# PCU.net
KiCad netlist of a schematic drawn in EAGLE
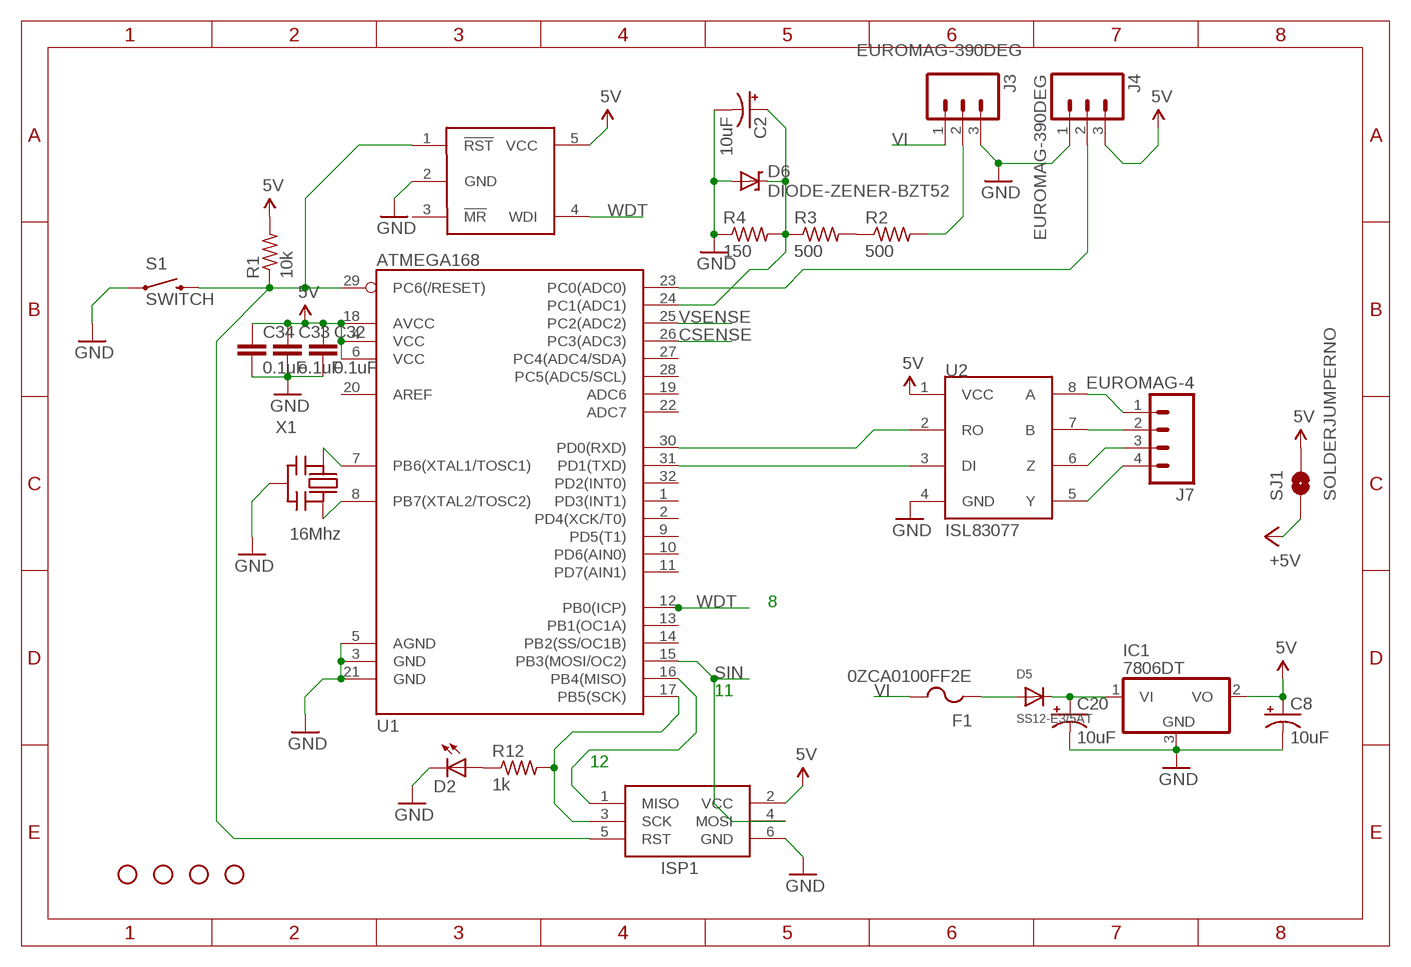
[diagram p0: schematic, sheet 1]
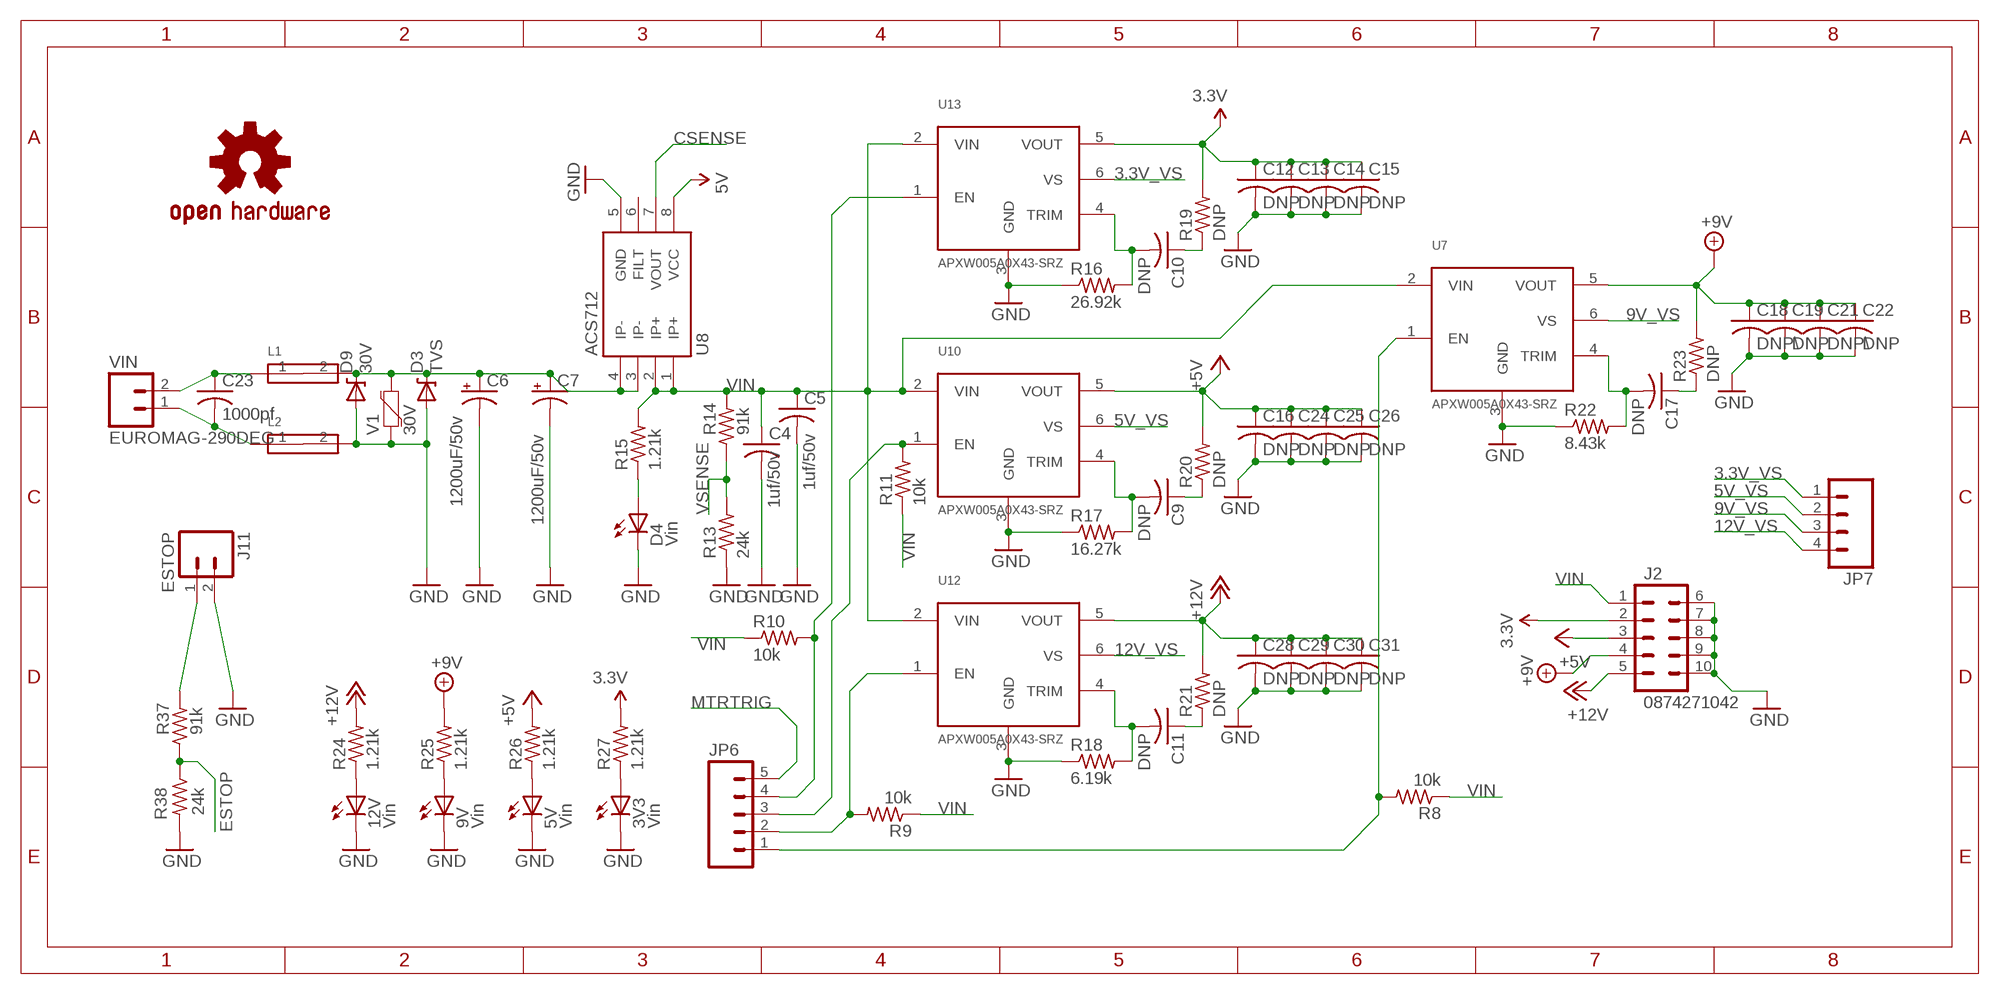
[diagram p1: schematic, sheet 2]
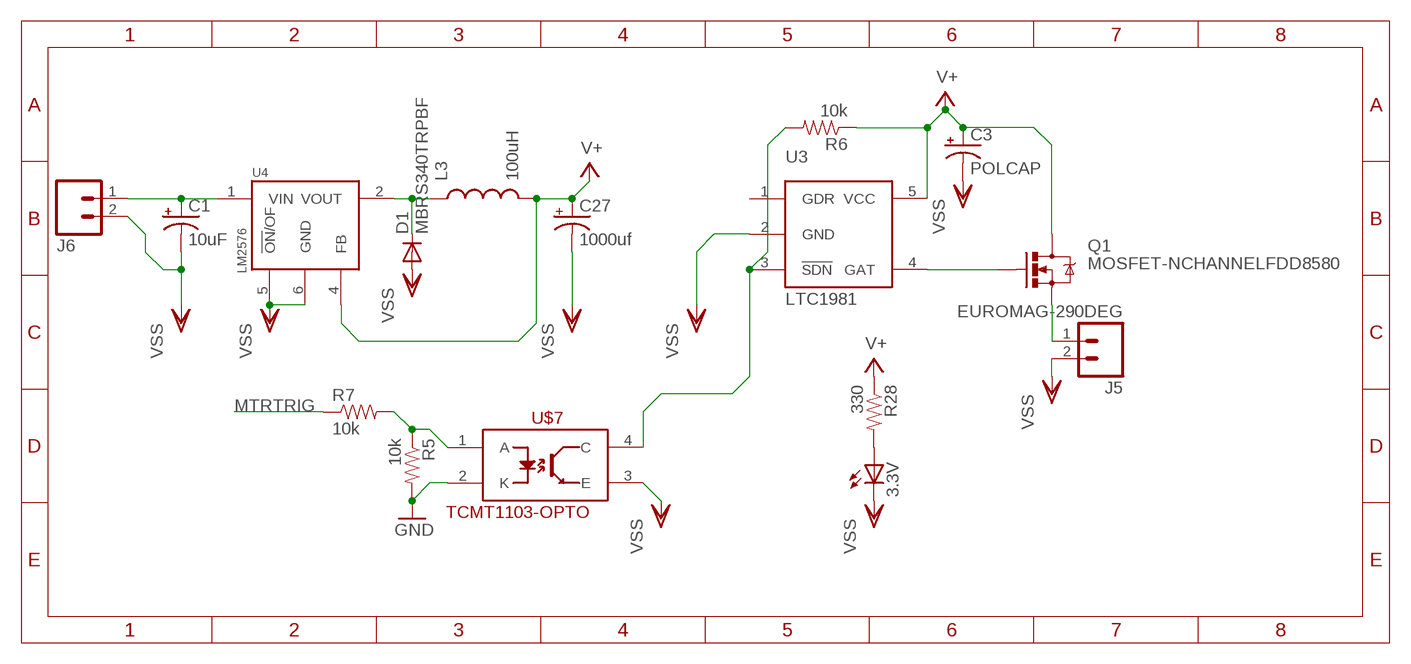
[diagram p2: schematic, sheet 3]

(export (version "E")
  (design (tool "Eeschema 10.0.6"))
  (components
    (comp (ref "C2")
      (value "10uF")
      (footprint "eagle-import:EIA3216")
      (libsource (lib "eagle-import") (part "CAP_POL1206"))
    )
    (comp (ref "C8")
      (value "10uF")
      (footprint "eagle-import:CT6032")
      (libsource (lib "eagle-import") (part "CPOL-USCT6032"))
    )
    (comp (ref "C20")
      (value "10uF")
      (footprint "eagle-import:CT6032")
      (libsource (lib "eagle-import") (part "CPOL-USCT6032"))
    )
    (comp (ref "C32")
      (value "0.1uF")
      (footprint "eagle-import:0805")
      (libsource (lib "eagle-import") (part "CAP0805"))
    )
    (comp (ref "C33")
      (value "o.1uF")
      (footprint "eagle-import:0805")
      (libsource (lib "eagle-import") (part "CAP0805"))
    )
    (comp (ref "C34")
      (value "0.1uF")
      (footprint "eagle-import:0805")
      (libsource (lib "eagle-import") (part "CAP0805"))
    )
    (comp (ref "D2")
      (value "LEDCHIPLED_0805")
      (footprint "eagle-import:CHIPLED_0805")
      (libsource (lib "eagle-import") (part "LEDCHIPLED_0805"))
    )
    (comp (ref "D5")
      (value "SS12-E3/5AT")
      (footprint "eagle-import:SMADIODE")
      (libsource (lib "eagle-import") (part "DIODESMA"))
    )
    (comp (ref "D6")
      (value "DIODE-ZENER-BZT52")
      (footprint "eagle-import:SOD-323")
      (libsource (lib "eagle-import") (part "DIODE-ZENER-BZT52"))
    )
    (comp (ref "F1")
      (value "0ZCA0100FF2E")
      (footprint "eagle-import:R1206")
      (libsource (lib "eagle-import") (part "PTCFUSE-1206"))
    )
    (comp (ref "IC1")
      (value "7806DT")
      (footprint "eagle-import:TO252")
      (libsource (lib "eagle-import") (part "78DT06"))
    )
    (comp (ref "ISP1")
      (value "AVRISP-6")
      (footprint "eagle-import:AVRISP")
      (libsource (lib "eagle-import") (part "AVRISP-6"))
    )
    (comp (ref "J3")
      (value "EUROMAG-390DEG")
      (footprint "eagle-import:M3")
      (libsource (lib "eagle-import") (part "EUROMAG-390DEG"))
    )
    (comp (ref "J4")
      (value "EUROMAG-390DEG")
      (footprint "eagle-import:M3")
      (libsource (lib "eagle-import") (part "EUROMAG-390DEG"))
    )
    (comp (ref "J7")
      (value "EUROMAG-4")
      (footprint "eagle-import:M4")
      (libsource (lib "eagle-import") (part "EUROMAG-4"))
    )
    (comp (ref "JP1")
      (value "STAND-OFF")
      (footprint "eagle-import:STAND-OFF")
      (libsource (lib "eagle-import") (part "STAND-OFF"))
    )
    (comp (ref "JP3")
      (value "STAND-OFF")
      (footprint "eagle-import:STAND-OFF")
      (libsource (lib "eagle-import") (part "STAND-OFF"))
    )
    (comp (ref "JP4")
      (value "STAND-OFF")
      (footprint "eagle-import:STAND-OFF")
      (libsource (lib "eagle-import") (part "STAND-OFF"))
    )
    (comp (ref "JP5")
      (value "STAND-OFF")
      (footprint "eagle-import:STAND-OFF")
      (libsource (lib "eagle-import") (part "STAND-OFF"))
    )
    (comp (ref "R1")
      (value "10k")
      (footprint "eagle-import:M0805")
      (libsource (lib "eagle-import") (part "R-US_M0805"))
    )
    (comp (ref "R2")
      (value "500")
      (footprint "eagle-import:M0805")
      (libsource (lib "eagle-import") (part "R-US_M0805"))
    )
    (comp (ref "R3")
      (value "500")
      (footprint "eagle-import:M0805")
      (libsource (lib "eagle-import") (part "R-US_M0805"))
    )
    (comp (ref "R4")
      (value "150")
      (footprint "eagle-import:M0805")
      (libsource (lib "eagle-import") (part "R-US_M0805"))
    )
    (comp (ref "R12")
      (value "1k")
      (footprint "eagle-import:M0805")
      (libsource (lib "eagle-import") (part "R-US_M0805"))
    )
    (comp (ref "S1")
      (value "SWITCH")
      (footprint "eagle-import:TACTILE-PTH")
      (libsource (lib "eagle-import") (part "SWITCH-MOMENTARY-2PTH"))
    )
    (comp (ref "SJ1")
      (value "SOLDERJUMPERNO")
      (footprint "eagle-import:SJ_2S-NO")
      (libsource (lib "eagle-import") (part "SOLDERJUMPERNO"))
    )
    (comp (ref "U1")
      (value "ATMEGA168")
      (footprint "eagle-import:TQFP32-08")
      (libsource (lib "eagle-import") (part "ATMEGA168"))
    )
    (comp (ref "U2")
      (value "ISL83077")
      (footprint "eagle-import:SO08")
      (libsource (lib "eagle-import") (part "ISL83077"))
    )
    (comp (ref "U14")
      (value "MAX823")
      (footprint "eagle-import:SOT23-5L")
      (libsource (lib "eagle-import") (part "MAX823"))
    )
    (comp (ref "X1")
      (value "16Mhz")
      (footprint "eagle-import:AWCSR")
      (libsource (lib "eagle-import") (part "CERMOSCILL-AWCSR"))
    )
    (comp (ref "3V3")
      (value "Vin")
      (footprint "eagle-import:CHIP-LED0805")
      (libsource (lib "eagle-import") (part "LEDCHIP-LED0805"))
    )
    (comp (ref "5V")
      (value "Vin")
      (footprint "eagle-import:CHIP-LED0805")
      (libsource (lib "eagle-import") (part "LEDCHIP-LED0805"))
    )
    (comp (ref "9V")
      (value "Vin")
      (footprint "eagle-import:CHIP-LED0805")
      (libsource (lib "eagle-import") (part "LEDCHIP-LED0805"))
    )
    (comp (ref "12V")
      (value "Vin")
      (footprint "eagle-import:CHIP-LED0805")
      (libsource (lib "eagle-import") (part "LEDCHIP-LED0805"))
    )
    (comp (ref "C4")
      (value "1uf/50v")
      (footprint "eagle-import:C0805")
      (libsource (lib "eagle-import") (part "C-USC0805"))
    )
    (comp (ref "C5")
      (value "1uf/50v")
      (footprint "eagle-import:C0805")
      (libsource (lib "eagle-import") (part "C-USC0805"))
    )
    (comp (ref "C6")
      (value "1200uF/50v")
      (footprint "eagle-import:CAN_18MM")
      (libsource (lib "eagle-import") (part "CAP_CAN1"))
    )
    (comp (ref "C7")
      (value "1200uF/50v")
      (footprint "eagle-import:CAN_18MM")
      (libsource (lib "eagle-import") (part "CAP_CAN1"))
    )
    (comp (ref "C9")
      (value "DNP")
      (footprint "eagle-import:C0805")
      (libsource (lib "eagle-import") (part "C-USC0805"))
    )
    (comp (ref "C10")
      (value "DNP")
      (footprint "eagle-import:C0805")
      (libsource (lib "eagle-import") (part "C-USC0805"))
    )
    (comp (ref "C11")
      (value "DNP")
      (footprint "eagle-import:C0805")
      (libsource (lib "eagle-import") (part "C-USC0805"))
    )
    (comp (ref "C12")
      (value "DNP")
      (footprint "eagle-import:C0805")
      (libsource (lib "eagle-import") (part "C-USC0805"))
    )
    (comp (ref "C13")
      (value "DNP")
      (footprint "eagle-import:C0805")
      (libsource (lib "eagle-import") (part "C-USC0805"))
    )
    (comp (ref "C14")
      (value "DNP")
      (footprint "eagle-import:C0805")
      (libsource (lib "eagle-import") (part "C-USC0805"))
    )
    (comp (ref "C15")
      (value "DNP")
      (footprint "eagle-import:C0805")
      (libsource (lib "eagle-import") (part "C-USC0805"))
    )
    (comp (ref "C16")
      (value "DNP")
      (footprint "eagle-import:C0805")
      (libsource (lib "eagle-import") (part "C-USC0805"))
    )
    (comp (ref "C17")
      (value "DNP")
      (footprint "eagle-import:C0805")
      (libsource (lib "eagle-import") (part "C-USC0805"))
    )
    (comp (ref "C18")
      (value "DNP\\")
      (footprint "eagle-import:C0805")
      (libsource (lib "eagle-import") (part "C-USC0805"))
    )
    (comp (ref "C19")
      (value "DNP")
      (footprint "eagle-import:C0805")
      (libsource (lib "eagle-import") (part "C-USC0805"))
    )
    (comp (ref "C21")
      (value "DNP\\")
      (footprint "eagle-import:C0805")
      (libsource (lib "eagle-import") (part "C-USC0805"))
    )
    (comp (ref "C22")
      (value "DNP")
      (footprint "eagle-import:C0805")
      (libsource (lib "eagle-import") (part "C-USC0805"))
    )
    (comp (ref "C23")
      (value "1000pf")
      (footprint "eagle-import:C1825")
      (libsource (lib "eagle-import") (part "C-USC1825"))
    )
    (comp (ref "C24")
      (value "DNP")
      (footprint "eagle-import:C0805")
      (libsource (lib "eagle-import") (part "C-USC0805"))
    )
    (comp (ref "C25")
      (value "DNP")
      (footprint "eagle-import:C0805")
      (libsource (lib "eagle-import") (part "C-USC0805"))
    )
    (comp (ref "C26")
      (value "DNP")
      (footprint "eagle-import:C0805")
      (libsource (lib "eagle-import") (part "C-USC0805"))
    )
    (comp (ref "C28")
      (value "DNP")
      (footprint "eagle-import:C0805")
      (libsource (lib "eagle-import") (part "C-USC0805"))
    )
    (comp (ref "C29")
      (value "DNP")
      (footprint "eagle-import:C0805")
      (libsource (lib "eagle-import") (part "C-USC0805"))
    )
    (comp (ref "C30")
      (value "DNP")
      (footprint "eagle-import:C0805")
      (libsource (lib "eagle-import") (part "C-USC0805"))
    )
    (comp (ref "C31")
      (value "DNP")
      (footprint "eagle-import:C0805")
      (libsource (lib "eagle-import") (part "C-USC0805"))
    )
    (comp (ref "D3")
      (value "TVS")
      (footprint "eagle-import:DO-214AC")
      (libsource (lib "eagle-import") (part "TVS"))
    )
    (comp (ref "D4")
      (value "Vin")
      (footprint "eagle-import:CHIP-LED0805")
      (libsource (lib "eagle-import") (part "LEDCHIP-LED0805"))
    )
    (comp (ref "D9")
      (value "30V")
      (footprint "eagle-import:SMB-DIODE")
      (libsource (lib "eagle-import") (part "DIODE-ZENERSMB"))
    )
    (comp (ref "J2")
      (value "0874271042")
      (footprint "eagle-import:0874271042")
      (libsource (lib "eagle-import") (part "0874271042"))
    )
    (comp (ref "J11")
      (value "ESTOP")
      (footprint "eagle-import:M2")
      (libsource (lib "eagle-import") (part "EUROMAG-290DEG"))
    )
    (comp (ref "JP6")
      (value "M05PTH_LONGPADS")
      (footprint "eagle-import:1X05_LONGPADS")
      (libsource (lib "eagle-import") (part "M05PTH_LONGPADS"))
    )
    (comp (ref "JP7")
      (value "M04POLAR")
      (footprint "eagle-import:MOLEX-1X4")
      (libsource (lib "eagle-import") (part "M04POLAR"))
    )
    (comp (ref "L1")
      (value "FERITEBEAD")
      (footprint "eagle-import:0603")
      (libsource (lib "eagle-import") (part "FERITEBEAD"))
    )
    (comp (ref "L2")
      (value "FERITEBEAD")
      (footprint "eagle-import:0603")
      (libsource (lib "eagle-import") (part "FERITEBEAD"))
    )
    (comp (ref "R8")
      (value "10k")
      (footprint "eagle-import:R0805")
      (libsource (lib "eagle-import") (part "R-US_R0805"))
    )
    (comp (ref "R9")
      (value "10k")
      (footprint "eagle-import:R0805")
      (libsource (lib "eagle-import") (part "R-US_R0805"))
    )
    (comp (ref "R10")
      (value "10k")
      (footprint "eagle-import:R0805")
      (libsource (lib "eagle-import") (part "R-US_R0805"))
    )
    (comp (ref "R11")
      (value "10k")
      (footprint "eagle-import:R0805")
      (libsource (lib "eagle-import") (part "R-US_R0805"))
    )
    (comp (ref "R13")
      (value "24k")
      (footprint "eagle-import:R0805")
      (libsource (lib "eagle-import") (part "R-US_R0805"))
    )
    (comp (ref "R14")
      (value "91k")
      (footprint "eagle-import:R0805")
      (libsource (lib "eagle-import") (part "R-US_R0805"))
    )
    (comp (ref "R15")
      (value "1.21k")
      (footprint "eagle-import:R0805")
      (libsource (lib "eagle-import") (part "R-US_R0805"))
    )
    (comp (ref "R16")
      (value "26.92k")
      (footprint "eagle-import:R0805")
      (libsource (lib "eagle-import") (part "R-US_R0805"))
    )
    (comp (ref "R17")
      (value "16.27k")
      (footprint "eagle-import:R0805")
      (libsource (lib "eagle-import") (part "R-US_R0805"))
    )
    (comp (ref "R18")
      (value "6.19k")
      (footprint "eagle-import:R0805")
      (libsource (lib "eagle-import") (part "R-US_R0805"))
    )
    (comp (ref "R19")
      (value "DNP")
      (footprint "eagle-import:R0805")
      (libsource (lib "eagle-import") (part "R-US_R0805"))
    )
    (comp (ref "R20")
      (value "DNP")
      (footprint "eagle-import:R0805")
      (libsource (lib "eagle-import") (part "R-US_R0805"))
    )
    (comp (ref "R21")
      (value "DNP")
      (footprint "eagle-import:R0805")
      (libsource (lib "eagle-import") (part "R-US_R0805"))
    )
    (comp (ref "R22")
      (value "8.43k")
      (footprint "eagle-import:R0805")
      (libsource (lib "eagle-import") (part "R-US_R0805"))
    )
    (comp (ref "R23")
      (value "DNP")
      (footprint "eagle-import:R0805")
      (libsource (lib "eagle-import") (part "R-US_R0805"))
    )
    (comp (ref "R24")
      (value "1.21k")
      (footprint "eagle-import:R0805")
      (libsource (lib "eagle-import") (part "R-US_R0805"))
    )
    (comp (ref "R25")
      (value "1.21k")
      (footprint "eagle-import:R0805")
      (libsource (lib "eagle-import") (part "R-US_R0805"))
    )
    (comp (ref "R26")
      (value "1.21k")
      (footprint "eagle-import:R0805")
      (libsource (lib "eagle-import") (part "R-US_R0805"))
    )
    (comp (ref "R27")
      (value "1.21k")
      (footprint "eagle-import:R0805")
      (libsource (lib "eagle-import") (part "R-US_R0805"))
    )
    (comp (ref "R37")
      (value "91k")
      (footprint "eagle-import:R0805")
      (libsource (lib "eagle-import") (part "R-US_R0805"))
    )
    (comp (ref "R38")
      (value "24k")
      (footprint "eagle-import:R0805")
      (libsource (lib "eagle-import") (part "R-US_R0805"))
    )
    (comp (ref "U$8")
      (value "OSHW-LOGOM")
      (footprint "eagle-import:OSHW-LOGO-M")
      (libsource (lib "eagle-import") (part "OSHW-LOGOM"))
    )
    (comp (ref "U7")
      (value "APXW005A0X43-SRZ")
      (footprint "eagle-import:APXW005A0X43-SRZ")
      (libsource (lib "eagle-import") (part "APXW005A0X43-SRZ"))
    )
    (comp (ref "U8")
      (value "ACS712")
      (footprint "eagle-import:SO08")
      (libsource (lib "eagle-import") (part "ACS712"))
    )
    (comp (ref "U10")
      (value "APXW005A0X43-SRZ")
      (footprint "eagle-import:APXW005A0X43-SRZ")
      (libsource (lib "eagle-import") (part "APXW005A0X43-SRZ"))
    )
    (comp (ref "U12")
      (value "APXW005A0X43-SRZ")
      (footprint "eagle-import:APXW005A0X43-SRZ")
      (libsource (lib "eagle-import") (part "APXW005A0X43-SRZ"))
    )
    (comp (ref "U13")
      (value "APXW005A0X43-SRZ")
      (footprint "eagle-import:APXW005A0X43-SRZ")
      (libsource (lib "eagle-import") (part "APXW005A0X43-SRZ"))
    )
    (comp (ref "V1")
      (value "30V")
      (footprint "eagle-import:0603-RES")
      (libsource (lib "eagle-import") (part "VARISTOR-0603"))
    )
    (comp (ref "VIN")
      (value "EUROMAG-290DEG")
      (footprint "eagle-import:M2")
      (libsource (lib "eagle-import") (part "EUROMAG-290DEG"))
    )
    (comp (ref "3.3V")
      (value "LEDCHIPLED_0805")
      (footprint "eagle-import:CHIPLED_0805")
      (libsource (lib "eagle-import") (part "LEDCHIPLED_0805"))
    )
    (comp (ref "C1")
      (value "10uF")
      (footprint "eagle-import:EIA7343")
      (libsource (lib "eagle-import") (part "CAP_POL7343"))
    )
    (comp (ref "C3")
      (value "POLCAP")
      (footprint "eagle-import:POLC1206")
      (libsource (lib "eagle-import") (part "POLCAP"))
    )
    (comp (ref "C27")
      (value "1000uf")
      (footprint "eagle-import:PANASONIC_G")
      (libsource (lib "eagle-import") (part "CAP_POLG"))
    )
    (comp (ref "D1")
      (value "MBRS340TRPBF")
      (footprint "eagle-import:SMC")
      (libsource (lib "eagle-import") (part "DIODE-SMC"))
    )
    (comp (ref "J5")
      (value "EUROMAG-290DEG")
      (footprint "eagle-import:M2")
      (libsource (lib "eagle-import") (part "EUROMAG-290DEG"))
    )
    (comp (ref "J6")
      (value "EUROMAG-290DEG")
      (footprint "eagle-import:M2")
      (libsource (lib "eagle-import") (part "EUROMAG-290DEG"))
    )
    (comp (ref "L3")
      (value "100uH")
      (footprint "eagle-import:INDUCTOR_5X3")
      (libsource (lib "eagle-import") (part "INDUCTOR"))
    )
    (comp (ref "Q1")
      (value "MOSFET-NCHANNELFDD8580")
      (footprint "eagle-import:DPAK")
      (libsource (lib "eagle-import") (part "MOSFET-NCHANNELFDD8580"))
    )
    (comp (ref "R5")
      (value "10k")
      (footprint "eagle-import:0805")
      (libsource (lib "eagle-import") (part "RESISTOR0805-RES"))
    )
    (comp (ref "R6")
      (value "10k")
      (footprint "eagle-import:0805")
      (libsource (lib "eagle-import") (part "RESISTOR0805-RES"))
    )
    (comp (ref "R7")
      (value "10k")
      (footprint "eagle-import:0805")
      (libsource (lib "eagle-import") (part "RESISTOR0805-RES"))
    )
    (comp (ref "R28")
      (value "330")
      (footprint "eagle-import:0805")
      (libsource (lib "eagle-import") (part "RESISTOR0805-RES"))
    )
    (comp (ref "U$7")
      (value "TCMT1103-OPTO")
      (footprint "eagle-import:SSOP-4")
      (libsource (lib "eagle-import") (part "TCMT1103-OPTO"))
    )
    (comp (ref "U3")
      (value "LTC1981")
      (footprint "eagle-import:SOT23-5L")
      (libsource (lib "eagle-import") (part "LTC1981"))
    )
    (comp (ref "U4")
      (value "LM2576")
      (footprint "eagle-import:TO-263-5")
      (libsource (lib "eagle-import") (part "LM2576"))
    )
  )
  (nets
    (net (code "1") (name "+5V") (class "Default")
      (node (ref "C16") (pin "1") (pinfunction "1_1") (pintype "passive"))
      (node (ref "C24") (pin "1") (pinfunction "1_1") (pintype "passive"))
      (node (ref "C25") (pin "1") (pinfunction "1_1") (pintype "passive"))
      (node (ref "C26") (pin "1") (pinfunction "1_1") (pintype "passive"))
      (node (ref "J2") (pin "3") (pinfunction "3_3") (pintype "passive"))
      (node (ref "R20") (pin "2") (pinfunction "2_2") (pintype "passive"))
      (node (ref "R26") (pin "2") (pinfunction "2_2") (pintype "passive"))
      (node (ref "SJ1") (pin "1") (pinfunction "1_1") (pintype "passive"))
      (node (ref "U10") (pin "5") (pinfunction "VOUT_5") (pintype "bidirectional"))
    )
    (net (code "2") (name "+9V") (class "Default")
      (node (ref "C18") (pin "1") (pinfunction "1_1") (pintype "passive"))
      (node (ref "C19") (pin "1") (pinfunction "1_1") (pintype "passive"))
      (node (ref "C21") (pin "1") (pinfunction "1_1") (pintype "passive"))
      (node (ref "C22") (pin "1") (pinfunction "1_1") (pintype "passive"))
      (node (ref "J2") (pin "4") (pinfunction "4_4") (pintype "passive"))
      (node (ref "R23") (pin "2") (pinfunction "2_2") (pintype "passive"))
      (node (ref "R25") (pin "2") (pinfunction "2_2") (pintype "passive"))
      (node (ref "U7") (pin "5") (pinfunction "VOUT_5") (pintype "bidirectional"))
    )
    (net (code "3") (name "+12V") (class "Default")
      (node (ref "C28") (pin "1") (pinfunction "1_1") (pintype "passive"))
      (node (ref "C29") (pin "1") (pinfunction "1_1") (pintype "passive"))
      (node (ref "C30") (pin "1") (pinfunction "1_1") (pintype "passive"))
      (node (ref "C31") (pin "1") (pinfunction "1_1") (pintype "passive"))
      (node (ref "J2") (pin "5") (pinfunction "5_5") (pintype "passive"))
      (node (ref "R21") (pin "2") (pinfunction "2_2") (pintype "passive"))
      (node (ref "R24") (pin "2") (pinfunction "2_2") (pintype "passive"))
      (node (ref "U12") (pin "5") (pinfunction "VOUT_5") (pintype "bidirectional"))
    )
    (net (code "4") (name "3.3V") (class "Default")
      (node (ref "C12") (pin "1") (pinfunction "1_1") (pintype "passive"))
      (node (ref "C13") (pin "1") (pinfunction "1_1") (pintype "passive"))
      (node (ref "C14") (pin "1") (pinfunction "1_1") (pintype "passive"))
      (node (ref "C15") (pin "1") (pinfunction "1_1") (pintype "passive"))
      (node (ref "J2") (pin "2") (pinfunction "2_2") (pintype "passive"))
      (node (ref "R19") (pin "2") (pinfunction "2_2") (pintype "passive"))
      (node (ref "R27") (pin "2") (pinfunction "2_2") (pintype "passive"))
      (node (ref "U13") (pin "5") (pinfunction "VOUT_5") (pintype "bidirectional"))
    )
    (net (code "5") (name "3.3V_VS") (class "Default")
      (node (ref "JP7") (pin "1") (pinfunction "1_1") (pintype "passive"))
      (node (ref "U13") (pin "6") (pinfunction "VS_6") (pintype "bidirectional"))
    )
    (net (code "6") (name "5V") (class "Default")
      (node (ref "C32") (pin "1") (pinfunction "1_1") (pintype "passive"))
      (node (ref "C33") (pin "1") (pinfunction "1_1") (pintype "passive"))
      (node (ref "C34") (pin "1") (pinfunction "1_1") (pintype "passive"))
      (node (ref "C8") (pin "+") (pinfunction "+_+") (pintype "passive"))
      (node (ref "IC1") (pin "2") (pinfunction "VO_2") (pintype "passive"))
      (node (ref "ISP1") (pin "2") (pinfunction "VCC_2") (pintype "power_in"))
      (node (ref "J4") (pin "3") (pinfunction "3_3") (pintype "passive"))
      (node (ref "R1") (pin "2") (pinfunction "2_2") (pintype "passive"))
      (node (ref "SJ1") (pin "2") (pinfunction "2_2") (pintype "passive"))
      (node (ref "U1") (pin "18") (pinfunction "AVCC_18") (pintype "bidirectional"))
      (node (ref "U1") (pin "4") (pinfunction "VCC_4") (pintype "bidirectional"))
      (node (ref "U1") (pin "6") (pinfunction "VCC_6") (pintype "bidirectional"))
      (node (ref "U14") (pin "5") (pinfunction "VCC_5") (pintype "bidirectional"))
      (node (ref "U2") (pin "1") (pinfunction "VCC_1") (pintype "bidirectional"))
      (node (ref "U8") (pin "8") (pinfunction "VCC_8") (pintype "bidirectional"))
    )
    (net (code "7") (name "5V_VS") (class "Default")
      (node (ref "JP7") (pin "2") (pinfunction "2_2") (pintype "passive"))
      (node (ref "U10") (pin "6") (pinfunction "VS_6") (pintype "bidirectional"))
    )
    (net (code "8") (name "9V_VS") (class "Default")
      (node (ref "JP7") (pin "3") (pinfunction "3_3") (pintype "passive"))
      (node (ref "U7") (pin "6") (pinfunction "VS_6") (pintype "bidirectional"))
    )
    (net (code "9") (name "12V_VS") (class "Default")
      (node (ref "JP7") (pin "4") (pinfunction "4_4") (pintype "passive"))
      (node (ref "U12") (pin "6") (pinfunction "VS_6") (pintype "bidirectional"))
    )
    (net (code "10") (name "CSENSE") (class "Default")
      (node (ref "U1") (pin "26") (pinfunction "PC3(ADC3)_26") (pintype "bidirectional"))
      (node (ref "U8") (pin "7") (pinfunction "VOUT_7") (pintype "bidirectional"))
    )
    (net (code "11") (name "ESTOP") (class "Default")
      (node (ref "R37") (pin "1") (pinfunction "1_1") (pintype "passive"))
      (node (ref "R38") (pin "1") (pinfunction "1_1") (pintype "passive"))
    )
    (net (code "12") (name "GND") (class "Default")
      (node (ref "12V") (pin "C") (pinfunction "C_C") (pintype "passive"))
      (node (ref "3V3") (pin "C") (pinfunction "C_C") (pintype "passive"))
      (node (ref "5V") (pin "C") (pinfunction "C_C") (pintype "passive"))
      (node (ref "9V") (pin "C") (pinfunction "C_C") (pintype "passive"))
      (node (ref "C12") (pin "2") (pinfunction "2_2") (pintype "passive"))
      (node (ref "C13") (pin "2") (pinfunction "2_2") (pintype "passive"))
      (node (ref "C14") (pin "2") (pinfunction "2_2") (pintype "passive"))
      (node (ref "C15") (pin "2") (pinfunction "2_2") (pintype "passive"))
      (node (ref "C16") (pin "2") (pinfunction "2_2") (pintype "passive"))
      (node (ref "C18") (pin "2") (pinfunction "2_2") (pintype "passive"))
      (node (ref "C19") (pin "2") (pinfunction "2_2") (pintype "passive"))
      (node (ref "C2") (pin "C") (pinfunction "-_C") (pintype "passive"))
      (node (ref "C20") (pin "-") (pinfunction "-_-") (pintype "passive"))
      (node (ref "C21") (pin "2") (pinfunction "2_2") (pintype "passive"))
      (node (ref "C22") (pin "2") (pinfunction "2_2") (pintype "passive"))
      (node (ref "C24") (pin "2") (pinfunction "2_2") (pintype "passive"))
      (node (ref "C25") (pin "2") (pinfunction "2_2") (pintype "passive"))
      (node (ref "C26") (pin "2") (pinfunction "2_2") (pintype "passive"))
      (node (ref "C28") (pin "2") (pinfunction "2_2") (pintype "passive"))
      (node (ref "C29") (pin "2") (pinfunction "2_2") (pintype "passive"))
      (node (ref "C30") (pin "2") (pinfunction "2_2") (pintype "passive"))
      (node (ref "C31") (pin "2") (pinfunction "2_2") (pintype "passive"))
      (node (ref "C32") (pin "2") (pinfunction "2_2") (pintype "passive"))
      (node (ref "C33") (pin "2") (pinfunction "2_2") (pintype "passive"))
      (node (ref "C34") (pin "2") (pinfunction "2_2") (pintype "passive"))
      (node (ref "C4") (pin "2") (pinfunction "2_2") (pintype "passive"))
      (node (ref "C5") (pin "2") (pinfunction "2_2") (pintype "passive"))
      (node (ref "C6") (pin "-") (pinfunction "-_-") (pintype "passive"))
      (node (ref "C7") (pin "-") (pinfunction "-_-") (pintype "passive"))
      (node (ref "C8") (pin "-") (pinfunction "-_-") (pintype "passive"))
      (node (ref "D2") (pin "C") (pinfunction "C_C") (pintype "passive"))
      (node (ref "D3") (pin "A") (pinfunction "A_A") (pintype "passive"))
      (node (ref "D4") (pin "C") (pinfunction "C_C") (pintype "passive"))
      (node (ref "D6") (pin "2") (pinfunction "A_2") (pintype "passive"))
      (node (ref "D9") (pin "A") (pinfunction "A_A") (pintype "passive"))
      (node (ref "IC1") (pin "3") (pinfunction "GND_3") (pintype "passive"))
      (node (ref "ISP1") (pin "6") (pinfunction "GND_6") (pintype "power_in"))
      (node (ref "J11") (pin "2") (pinfunction "2_2") (pintype "passive"))
      (node (ref "J2") (pin "10") (pinfunction "10_10") (pintype "passive"))
      (node (ref "J2") (pin "6") (pinfunction "6_6") (pintype "passive"))
      (node (ref "J2") (pin "7") (pinfunction "7_7") (pintype "passive"))
      (node (ref "J2") (pin "8") (pinfunction "8_8") (pintype "passive"))
      (node (ref "J2") (pin "9") (pinfunction "9_9") (pintype "passive"))
      (node (ref "J3") (pin "3") (pinfunction "3_3") (pintype "passive"))
      (node (ref "J4") (pin "1") (pinfunction "1_1") (pintype "passive"))
      (node (ref "L2") (pin "2") (pinfunction "P$2_2") (pintype "bidirectional"))
      (node (ref "R13") (pin "1") (pinfunction "1_1") (pintype "passive"))
      (node (ref "R16") (pin "1") (pinfunction "1_1") (pintype "passive"))
      (node (ref "R17") (pin "1") (pinfunction "1_1") (pintype "passive"))
      (node (ref "R18") (pin "1") (pinfunction "1_1") (pintype "passive"))
      (node (ref "R22") (pin "1") (pinfunction "1_1") (pintype "passive"))
      (node (ref "R38") (pin "2") (pinfunction "2_2") (pintype "passive"))
      (node (ref "R4") (pin "1") (pinfunction "1_1") (pintype "passive"))
      (node (ref "R5") (pin "2") (pinfunction "2_2") (pintype "passive"))
      (node (ref "S1") (pin "1") (pinfunction "1_1") (pintype "passive"))
      (node (ref "U$7") (pin "2") (pinfunction "K_2") (pintype "bidirectional"))
      (node (ref "U1") (pin "21") (pinfunction "GND_21") (pintype "bidirectional"))
      (node (ref "U1") (pin "3") (pinfunction "GND_3") (pintype "bidirectional"))
      (node (ref "U1") (pin "5") (pinfunction "AGND_5") (pintype "bidirectional"))
      (node (ref "U10") (pin "3") (pinfunction "GND_3") (pintype "bidirectional"))
      (node (ref "U12") (pin "3") (pinfunction "GND_3") (pintype "bidirectional"))
      (node (ref "U13") (pin "3") (pinfunction "GND_3") (pintype "bidirectional"))
      (node (ref "U14") (pin "2") (pinfunction "GND_2") (pintype "bidirectional"))
      (node (ref "U2") (pin "4") (pinfunction "GND_4") (pintype "bidirectional"))
      (node (ref "U7") (pin "3") (pinfunction "GND_3") (pintype "bidirectional"))
      (node (ref "U8") (pin "5") (pinfunction "GND_5") (pintype "bidirectional"))
      (node (ref "V1") (pin "1") (pinfunction "1_1") (pintype "passive"))
      (node (ref "X1") (pin "2") (pinfunction "GND_2") (pintype "bidirectional"))
    )
    (net (code "13") (name "MTRTRIG") (class "Default")
      (node (ref "JP6") (pin "5") (pinfunction "5_5") (pintype "passive"))
      (node (ref "R7") (pin "1") (pinfunction "1_1") (pintype "passive"))
    )
    (net (code "14") (name "Net-(3.3V-PadA)") (class "Default")
      (node (ref "3.3V") (pin "A") (pinfunction "A_A") (pintype "passive"))
      (node (ref "R28") (pin "2") (pinfunction "2_2") (pintype "passive"))
    )
    (net (code "15") (name "Net-(3V3-PadA)") (class "Default")
      (node (ref "3V3") (pin "A") (pinfunction "A_A") (pintype "passive"))
      (node (ref "R27") (pin "1") (pinfunction "1_1") (pintype "passive"))
    )
    (net (code "16") (name "Net-(5V-PadA)") (class "Default")
      (node (ref "5V") (pin "A") (pinfunction "A_A") (pintype "passive"))
      (node (ref "R26") (pin "1") (pinfunction "1_1") (pintype "passive"))
    )
    (net (code "17") (name "Net-(9V-PadA)") (class "Default")
      (node (ref "9V") (pin "A") (pinfunction "A_A") (pintype "passive"))
      (node (ref "R25") (pin "1") (pinfunction "1_1") (pintype "passive"))
    )
    (net (code "18") (name "Net-(12V-PadA)") (class "Default")
      (node (ref "12V") (pin "A") (pinfunction "A_A") (pintype "passive"))
      (node (ref "R24") (pin "1") (pinfunction "1_1") (pintype "passive"))
    )
    (net (code "19") (name "Net-(C1-+)") (class "Default")
      (node (ref "C1") (pin "A") (pinfunction "+_A") (pintype "passive"))
      (node (ref "J6") (pin "1") (pinfunction "1_1") (pintype "passive"))
      (node (ref "U4") (pin "1") (pinfunction "VIN_1") (pintype "power_in"))
    )
    (net (code "20") (name "Net-(C2-+)") (class "Default")
      (node (ref "C2") (pin "A") (pinfunction "+_A") (pintype "passive"))
      (node (ref "D6") (pin "1") (pinfunction "C_1") (pintype "passive"))
      (node (ref "R3") (pin "1") (pinfunction "1_1") (pintype "passive"))
      (node (ref "R4") (pin "2") (pinfunction "2_2") (pintype "passive"))
      (node (ref "U1") (pin "24") (pinfunction "PC1(ADC1)_24") (pintype "bidirectional"))
    )
    (net (code "21") (name "Net-(C9-Pad1)") (class "Default")
      (node (ref "C9") (pin "1") (pinfunction "1_1") (pintype "passive"))
      (node (ref "R20") (pin "1") (pinfunction "1_1") (pintype "passive"))
    )
    (net (code "22") (name "Net-(C10-Pad1)") (class "Default")
      (node (ref "C10") (pin "1") (pinfunction "1_1") (pintype "passive"))
      (node (ref "R19") (pin "1") (pinfunction "1_1") (pintype "passive"))
    )
    (net (code "23") (name "Net-(C11-Pad1)") (class "Default")
      (node (ref "C11") (pin "1") (pinfunction "1_1") (pintype "passive"))
      (node (ref "R21") (pin "1") (pinfunction "1_1") (pintype "passive"))
    )
    (net (code "24") (name "Net-(C17-Pad1)") (class "Default")
      (node (ref "C17") (pin "1") (pinfunction "1_1") (pintype "passive"))
      (node (ref "R23") (pin "1") (pinfunction "1_1") (pintype "passive"))
    )
    (net (code "25") (name "Net-(D2-PadA)") (class "Default")
      (node (ref "D2") (pin "A") (pinfunction "A_A") (pintype "passive"))
      (node (ref "R12") (pin "1") (pinfunction "1_1") (pintype "passive"))
    )
    (net (code "26") (name "Net-(D4-PadA)") (class "Default")
      (node (ref "D4") (pin "A") (pinfunction "A_A") (pintype "passive"))
      (node (ref "R15") (pin "1") (pinfunction "1_1") (pintype "passive"))
    )
    (net (code "27") (name "Net-(D5-PadA)") (class "Default")
      (node (ref "D5") (pin "A") (pinfunction "A_A") (pintype "passive"))
      (node (ref "F1") (pin "1") (pinfunction "1_1") (pintype "passive"))
    )
    (net (code "28") (name "Net-(IC1-VI)") (class "Default")
      (node (ref "C20") (pin "+") (pinfunction "+_+") (pintype "passive"))
      (node (ref "D5") (pin "C") (pinfunction "C_C") (pintype "passive"))
      (node (ref "IC1") (pin "1") (pinfunction "VI_1") (pintype "input"))
    )
    (net (code "29") (name "Net-(ISP1-MISO)") (class "Default")
      (node (ref "ISP1") (pin "1") (pinfunction "MISO_1") (pintype "input"))
      (node (ref "U1") (pin "16") (pinfunction "PB4(MISO)_16") (pintype "bidirectional"))
    )
    (net (code "30") (name "Net-(ISP1-RST)") (class "Default")
      (node (ref "ISP1") (pin "5") (pinfunction "RST_5") (pintype "output"))
      (node (ref "R1") (pin "1") (pinfunction "1_1") (pintype "passive"))
      (node (ref "S1") (pin "3") (pinfunction "2_3") (pintype "passive"))
      (node (ref "U1") (pin "29") (pinfunction "PC6(/RESET)_29") (pintype "bidirectional"))
      (node (ref "U14") (pin "1") (pinfunction "~{RST}_1") (pintype "bidirectional"))
    )
    (net (code "31") (name "Net-(ISP1-SCK)") (class "Default")
      (node (ref "ISP1") (pin "3") (pinfunction "SCK_3") (pintype "output"))
      (node (ref "R12") (pin "2") (pinfunction "2_2") (pintype "passive"))
      (node (ref "U1") (pin "17") (pinfunction "PB5(SCK)_17") (pintype "bidirectional"))
    )
    (net (code "32") (name "Net-(J3-Pad2)") (class "Default")
      (node (ref "J3") (pin "2") (pinfunction "2_2") (pintype "passive"))
      (node (ref "R2") (pin "2") (pinfunction "2_2") (pintype "passive"))
    )
    (net (code "33") (name "Net-(J11-Pad1)") (class "Default")
      (node (ref "J11") (pin "1") (pinfunction "1_1") (pintype "passive"))
      (node (ref "R37") (pin "2") (pinfunction "2_2") (pintype "passive"))
    )
    (net (code "34") (name "Net-(L1-P$1)") (class "Default")
      (node (ref "C23") (pin "1") (pinfunction "1_1") (pintype "passive"))
      (node (ref "L1") (pin "1") (pinfunction "P$1_1") (pintype "bidirectional"))
      (node (ref "VIN") (pin "2") (pinfunction "2_2") (pintype "passive"))
    )
    (net (code "35") (name "Net-(L1-P$2)") (class "Default")
      (node (ref "C6") (pin "+") (pinfunction "+_+") (pintype "passive"))
      (node (ref "C7") (pin "+") (pinfunction "+_+") (pintype "passive"))
      (node (ref "D3") (pin "C") (pinfunction "C_C") (pintype "passive"))
      (node (ref "D9") (pin "C") (pinfunction "C_C") (pintype "passive"))
      (node (ref "L1") (pin "2") (pinfunction "P$2_2") (pintype "bidirectional"))
      (node (ref "U8") (pin "3") (pinfunction "IP-_3") (pintype "bidirectional"))
      (node (ref "U8") (pin "4") (pinfunction "IP-_4") (pintype "bidirectional"))
      (node (ref "V1") (pin "2") (pinfunction "2_2") (pintype "passive"))
    )
    (net (code "36") (name "Net-(L2-P$1)") (class "Default")
      (node (ref "C23") (pin "2") (pinfunction "2_2") (pintype "passive"))
      (node (ref "L2") (pin "1") (pinfunction "P$1_1") (pintype "bidirectional"))
      (node (ref "VIN") (pin "1") (pinfunction "1_1") (pintype "passive"))
    )
    (net (code "37") (name "Net-(Q1-G)") (class "Default")
      (node (ref "Q1") (pin "1") (pinfunction "G_1") (pintype "passive"))
      (node (ref "U3") (pin "4") (pinfunction "GAT_4") (pintype "bidirectional"))
    )
    (net (code "38") (name "Net-(Q1-S)") (class "Default")
      (node (ref "J5") (pin "1") (pinfunction "1_1") (pintype "passive"))
      (node (ref "Q1") (pin "3") (pinfunction "S_3") (pintype "passive"))
    )
    (net (code "39") (name "Net-(R2-Pad1)") (class "Default")
      (node (ref "R2") (pin "1") (pinfunction "1_1") (pintype "passive"))
      (node (ref "R3") (pin "2") (pinfunction "2_2") (pintype "passive"))
    )
    (net (code "40") (name "Net-(U$7-A)") (class "Default")
      (node (ref "R5") (pin "1") (pinfunction "1_1") (pintype "passive"))
      (node (ref "R7") (pin "2") (pinfunction "2_2") (pintype "passive"))
      (node (ref "U$7") (pin "1") (pinfunction "A_1") (pintype "bidirectional"))
    )
    (net (code "41") (name "Net-(U$7-C)") (class "Default")
      (node (ref "R6") (pin "2") (pinfunction "2_2") (pintype "passive"))
      (node (ref "U$7") (pin "4") (pinfunction "C_4") (pintype "bidirectional"))
      (node (ref "U3") (pin "3") (pinfunction "~{SDN}_3") (pintype "bidirectional"))
    )
    (net (code "42") (name "Net-(U1-PB6(XTAL1{slash}TOSC1))") (class "Default")
      (node (ref "U1") (pin "7") (pinfunction "PB6(XTAL1/TOSC1)_7") (pintype "bidirectional"))
      (node (ref "X1") (pin "1") (pinfunction "IN_1") (pintype "bidirectional"))
    )
    (net (code "43") (name "Net-(U1-PB7(XTAL2{slash}TOSC2))") (class "Default")
      (node (ref "U1") (pin "8") (pinfunction "PB7(XTAL2/TOSC2)_8") (pintype "bidirectional"))
      (node (ref "X1") (pin "3") (pinfunction "OUT_3") (pintype "bidirectional"))
    )
    (net (code "44") (name "Net-(U1-PC0(ADC0))") (class "Default")
      (node (ref "J4") (pin "2") (pinfunction "2_2") (pintype "passive"))
      (node (ref "U1") (pin "23") (pinfunction "PC0(ADC0)_23") (pintype "bidirectional"))
    )
    (net (code "45") (name "Net-(U1-PD0(RXD))") (class "Default")
      (node (ref "U1") (pin "30") (pinfunction "PD0(RXD)_30") (pintype "bidirectional"))
      (node (ref "U2") (pin "2") (pinfunction "RO_2") (pintype "bidirectional"))
    )
    (net (code "46") (name "Net-(U1-PD1(TXD))") (class "Default")
      (node (ref "U1") (pin "31") (pinfunction "PD1(TXD)_31") (pintype "bidirectional"))
      (node (ref "U2") (pin "3") (pinfunction "DI_3") (pintype "bidirectional"))
    )
    (net (code "47") (name "Net-(U2-A)") (class "Default")
      (node (ref "J7") (pin "1") (pinfunction "1_1") (pintype "passive"))
      (node (ref "U2") (pin "8") (pinfunction "A_8") (pintype "bidirectional"))
    )
    (net (code "48") (name "Net-(U2-B)") (class "Default")
      (node (ref "J7") (pin "2") (pinfunction "2_2") (pintype "passive"))
      (node (ref "U2") (pin "7") (pinfunction "B_7") (pintype "bidirectional"))
    )
    (net (code "49") (name "Net-(U2-Y)") (class "Default")
      (node (ref "J7") (pin "4") (pinfunction "4_4") (pintype "passive"))
      (node (ref "U2") (pin "5") (pinfunction "Y_5") (pintype "bidirectional"))
    )
    (net (code "50") (name "Net-(U2-Z)") (class "Default")
      (node (ref "J7") (pin "3") (pinfunction "3_3") (pintype "passive"))
      (node (ref "U2") (pin "6") (pinfunction "Z_6") (pintype "bidirectional"))
    )
    (net (code "51") (name "Net-(U4-VOUT)") (class "Default")
      (node (ref "D1") (pin "C") (pinfunction "C_C") (pintype "passive"))
      (node (ref "L3") (pin "1") (pinfunction "1_1") (pintype "passive"))
      (node (ref "U4") (pin "2") (pinfunction "VOUT_2") (pintype "power_in"))
    )
    (net (code "52") (name "Net-(U7-EN)") (class "Default")
      (node (ref "JP6") (pin "1") (pinfunction "1_1") (pintype "passive"))
      (node (ref "R8") (pin "2") (pinfunction "2_2") (pintype "passive"))
      (node (ref "U7") (pin "1") (pinfunction "EN_1") (pintype "bidirectional"))
    )
    (net (code "53") (name "Net-(U7-TRIM)") (class "Default")
      (node (ref "C17") (pin "2") (pinfunction "2_2") (pintype "passive"))
      (node (ref "R22") (pin "2") (pinfunction "2_2") (pintype "passive"))
      (node (ref "U7") (pin "4") (pinfunction "TRIM_4") (pintype "bidirectional"))
    )
    (net (code "54") (name "Net-(U10-EN)") (class "Default")
      (node (ref "JP6") (pin "3") (pinfunction "3_3") (pintype "passive"))
      (node (ref "R11") (pin "2") (pinfunction "2_2") (pintype "passive"))
      (node (ref "U10") (pin "1") (pinfunction "EN_1") (pintype "bidirectional"))
    )
    (net (code "55") (name "Net-(U10-TRIM)") (class "Default")
      (node (ref "C9") (pin "2") (pinfunction "2_2") (pintype "passive"))
      (node (ref "R17") (pin "2") (pinfunction "2_2") (pintype "passive"))
      (node (ref "U10") (pin "4") (pinfunction "TRIM_4") (pintype "bidirectional"))
    )
    (net (code "56") (name "Net-(U12-EN)") (class "Default")
      (node (ref "JP6") (pin "2") (pinfunction "2_2") (pintype "passive"))
      (node (ref "R9") (pin "2") (pinfunction "2_2") (pintype "passive"))
      (node (ref "U12") (pin "1") (pinfunction "EN_1") (pintype "bidirectional"))
    )
    (net (code "57") (name "Net-(U12-TRIM)") (class "Default")
      (node (ref "C11") (pin "2") (pinfunction "2_2") (pintype "passive"))
      (node (ref "R18") (pin "2") (pinfunction "2_2") (pintype "passive"))
      (node (ref "U12") (pin "4") (pinfunction "TRIM_4") (pintype "bidirectional"))
    )
    (net (code "58") (name "Net-(U13-EN)") (class "Default")
      (node (ref "JP6") (pin "4") (pinfunction "4_4") (pintype "passive"))
      (node (ref "R10") (pin "2") (pinfunction "2_2") (pintype "passive"))
      (node (ref "U13") (pin "1") (pinfunction "EN_1") (pintype "bidirectional"))
    )
    (net (code "59") (name "Net-(U13-TRIM)") (class "Default")
      (node (ref "C10") (pin "2") (pinfunction "2_2") (pintype "passive"))
      (node (ref "R16") (pin "2") (pinfunction "2_2") (pintype "passive"))
      (node (ref "U13") (pin "4") (pinfunction "TRIM_4") (pintype "bidirectional"))
    )
    (net (code "60") (name "SIN") (class "Default")
      (node (ref "ISP1") (pin "4") (pinfunction "MOSI_4") (pintype "output"))
      (node (ref "U1") (pin "15") (pinfunction "PB3(MOSI/OC2)_15") (pintype "bidirectional"))
    )
    (net (code "61") (name "V+") (class "Default")
      (node (ref "C27") (pin "+") (pinfunction "+_+") (pintype "passive"))
      (node (ref "C3") (pin "1") (pinfunction "+_1") (pintype "passive"))
      (node (ref "L3") (pin "2") (pinfunction "2_2") (pintype "passive"))
      (node (ref "Q1") (pin "4") (pinfunction "D_4") (pintype "passive"))
      (node (ref "R28") (pin "1") (pinfunction "1_1") (pintype "passive"))
      (node (ref "R6") (pin "1") (pinfunction "1_1") (pintype "passive"))
      (node (ref "U3") (pin "5") (pinfunction "VCC_5") (pintype "bidirectional"))
      (node (ref "U4") (pin "4") (pinfunction "FB_4") (pintype "power_in"))
    )
    (net (code "62") (name "VI") (class "Default")
      (node (ref "F1") (pin "2") (pinfunction "2_2") (pintype "passive"))
      (node (ref "J3") (pin "1") (pinfunction "1_1") (pintype "passive"))
    )
    (net (code "63") (name "VIN") (class "Default")
      (node (ref "C4") (pin "1") (pinfunction "1_1") (pintype "passive"))
      (node (ref "C5") (pin "1") (pinfunction "1_1") (pintype "passive"))
      (node (ref "J2") (pin "1") (pinfunction "1_1") (pintype "passive"))
      (node (ref "R10") (pin "1") (pinfunction "1_1") (pintype "passive"))
      (node (ref "R11") (pin "1") (pinfunction "1_1") (pintype "passive"))
      (node (ref "R14") (pin "2") (pinfunction "2_2") (pintype "passive"))
      (node (ref "R15") (pin "2") (pinfunction "2_2") (pintype "passive"))
      (node (ref "R8") (pin "1") (pinfunction "1_1") (pintype "passive"))
      (node (ref "R9") (pin "1") (pinfunction "1_1") (pintype "passive"))
      (node (ref "U10") (pin "2") (pinfunction "VIN_2") (pintype "bidirectional"))
      (node (ref "U12") (pin "2") (pinfunction "VIN_2") (pintype "bidirectional"))
      (node (ref "U13") (pin "2") (pinfunction "VIN_2") (pintype "bidirectional"))
      (node (ref "U7") (pin "2") (pinfunction "VIN_2") (pintype "bidirectional"))
      (node (ref "U8") (pin "1") (pinfunction "IP+_1") (pintype "bidirectional"))
      (node (ref "U8") (pin "2") (pinfunction "IP+_2") (pintype "bidirectional"))
    )
    (net (code "64") (name "VSENSE") (class "Default")
      (node (ref "R13") (pin "2") (pinfunction "2_2") (pintype "passive"))
      (node (ref "R14") (pin "1") (pinfunction "1_1") (pintype "passive"))
      (node (ref "U1") (pin "25") (pinfunction "PC2(ADC2)_25") (pintype "bidirectional"))
    )
    (net (code "65") (name "VSS") (class "Default")
      (node (ref "3.3V") (pin "C") (pinfunction "C_C") (pintype "passive"))
      (node (ref "C1") (pin "C") (pinfunction "-_C") (pintype "passive"))
      (node (ref "C27") (pin "-") (pinfunction "-_-") (pintype "passive"))
      (node (ref "C3") (pin "2") (pinfunction "-_2") (pintype "passive"))
      (node (ref "D1") (pin "A") (pinfunction "A_A") (pintype "passive"))
      (node (ref "J5") (pin "2") (pinfunction "2_2") (pintype "passive"))
      (node (ref "J6") (pin "2") (pinfunction "2_2") (pintype "passive"))
      (node (ref "U$7") (pin "3") (pinfunction "E_3") (pintype "bidirectional"))
      (node (ref "U3") (pin "2") (pinfunction "GND_2") (pintype "bidirectional"))
      (node (ref "U4") (pin "5") (pinfunction "~{ON}/OF_5") (pintype "bidirectional"))
      (node (ref "U4") (pin "6") (pinfunction "GND_6") (pintype "power_in"))
    )
    (net (code "66") (name "WDT") (class "Default")
      (node (ref "U1") (pin "12") (pinfunction "PB0(ICP)_12") (pintype "bidirectional"))
      (node (ref "U14") (pin "4") (pinfunction "WDI_4") (pintype "bidirectional"))
    )
    (net (code "67") (name "unconnected-(U1-ADC6-Pad19)") (class "Default")
      (node (ref "U1") (pin "19") (pinfunction "ADC6_19") (pintype "bidirectional"))
    )
    (net (code "68") (name "unconnected-(U1-ADC7-Pad22)") (class "Default")
      (node (ref "U1") (pin "22") (pinfunction "ADC7_22") (pintype "bidirectional"))
    )
    (net (code "69") (name "unconnected-(U1-AREF-Pad20)") (class "Default")
      (node (ref "U1") (pin "20") (pinfunction "AREF_20") (pintype "bidirectional"))
    )
    (net (code "70") (name "unconnected-(U1-PB1(OC1A)-Pad13)") (class "Default")
      (node (ref "U1") (pin "13") (pinfunction "PB1(OC1A)_13") (pintype "bidirectional"))
    )
    (net (code "71") (name "unconnected-(U1-PB2(SS{slash}OC1B)-Pad14)") (class "Default")
      (node (ref "U1") (pin "14") (pinfunction "PB2(SS/OC1B)_14") (pintype "bidirectional"))
    )
    (net (code "72") (name "unconnected-(U1-PC4(ADC4{slash}SDA)-Pad27)") (class "Default")
      (node (ref "U1") (pin "27") (pinfunction "PC4(ADC4/SDA)_27") (pintype "bidirectional"))
    )
    (net (code "73") (name "unconnected-(U1-PC5(ADC5{slash}SCL)-Pad28)") (class "Default")
      (node (ref "U1") (pin "28") (pinfunction "PC5(ADC5/SCL)_28") (pintype "bidirectional"))
    )
    (net (code "74") (name "unconnected-(U1-PD2(INT0)-Pad32)") (class "Default")
      (node (ref "U1") (pin "32") (pinfunction "PD2(INT0)_32") (pintype "bidirectional"))
    )
    (net (code "75") (name "unconnected-(U1-PD3(INT1)-Pad1)") (class "Default")
      (node (ref "U1") (pin "1") (pinfunction "PD3(INT1)_1") (pintype "bidirectional"))
    )
    (net (code "76") (name "unconnected-(U1-PD4(XCK{slash}T0)-Pad2)") (class "Default")
      (node (ref "U1") (pin "2") (pinfunction "PD4(XCK/T0)_2") (pintype "bidirectional"))
    )
    (net (code "77") (name "unconnected-(U1-PD5(T1)-Pad9)") (class "Default")
      (node (ref "U1") (pin "9") (pinfunction "PD5(T1)_9") (pintype "bidirectional"))
    )
    (net (code "78") (name "unconnected-(U1-PD6(AIN0)-Pad10)") (class "Default")
      (node (ref "U1") (pin "10") (pinfunction "PD6(AIN0)_10") (pintype "bidirectional"))
    )
    (net (code "79") (name "unconnected-(U1-PD7(AIN1)-Pad11)") (class "Default")
      (node (ref "U1") (pin "11") (pinfunction "PD7(AIN1)_11") (pintype "bidirectional"))
    )
    (net (code "80") (name "unconnected-(U3-GDR-Pad1)") (class "Default")
      (node (ref "U3") (pin "1") (pinfunction "GDR_1") (pintype "bidirectional"))
    )
    (net (code "81") (name "unconnected-(U8-FILT-Pad6)") (class "Default")
      (node (ref "U8") (pin "6") (pinfunction "FILT_6") (pintype "bidirectional"))
    )
    (net (code "82") (name "unconnected-(U14-~{MR}-Pad3)") (class "Default")
      (node (ref "U14") (pin "3") (pinfunction "~{MR}_3") (pintype "bidirectional"))
    )
  )
)
